# TemperaturaMagnetron.net
KiCad netlist of a schematic drawn in EAGLE
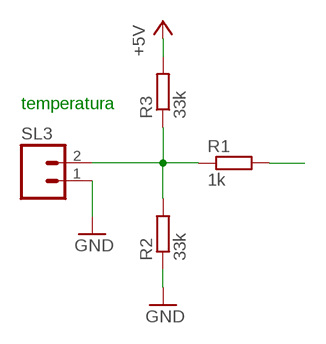
[diagram p0: schematic, sheet 1]

(export (version "E")
  (design (tool "Eeschema 10.0.6"))
  (components
    (comp (ref "R1")
      (value "1k")
      (footprint "eagle-import:0204_7")
      (libsource (lib "eagle-import") (part "R-EU_0204/7"))
    )
    (comp (ref "R2")
      (value "33k")
      (footprint "eagle-import:0204_7")
      (libsource (lib "eagle-import") (part "R-EU_0204/7"))
    )
    (comp (ref "R3")
      (value "33k")
      (footprint "eagle-import:0204_7")
      (libsource (lib "eagle-import") (part "R-EU_0204/7"))
    )
    (comp (ref "SL3")
      (value "M02")
      (footprint "eagle-import:02P")
      (libsource (lib "eagle-import") (part "M02"))
    )
  )
  (nets
    (net (code "1") (name "+5V") (class "Default")
      (node (ref "R3") (pin "2") (pinfunction "2_2") (pintype "passive"))
    )
    (net (code "2") (name "GND") (class "Default")
      (node (ref "R2") (pin "1") (pinfunction "1_1") (pintype "passive"))
      (node (ref "SL3") (pin "1") (pinfunction "1_1") (pintype "passive"))
    )
    (net (code "3") (name "Net-(R1-Pad1)") (class "Default")
      (node (ref "R1") (pin "1") (pinfunction "1_1") (pintype "passive"))
      (node (ref "R2") (pin "2") (pinfunction "2_2") (pintype "passive"))
      (node (ref "R3") (pin "1") (pinfunction "1_1") (pintype "passive"))
      (node (ref "SL3") (pin "2") (pinfunction "2_2") (pintype "passive"))
    )
    (net (code "4") (name "unconnected-(R1-Pad2)") (class "Default")
      (node (ref "R1") (pin "2") (pinfunction "2_2") (pintype "passive"))
    )
  )
)
